# DESERILIZER.net
KiCad netlist of a schematic drawn in Altium Designer
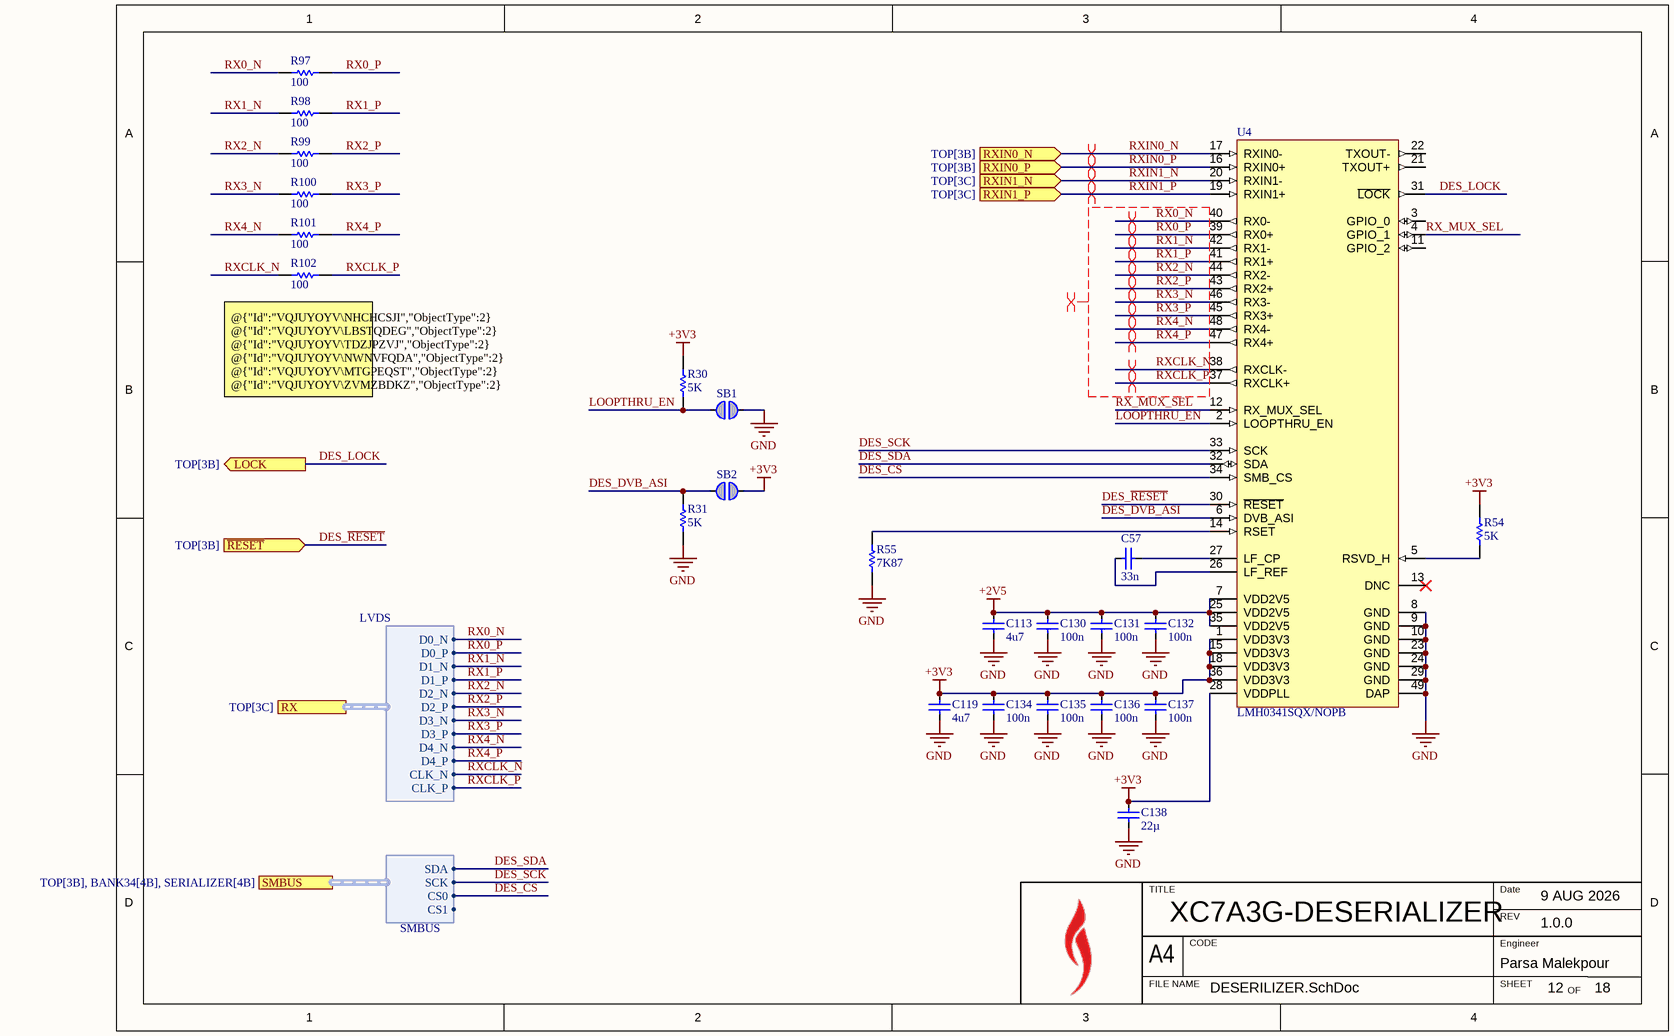
[diagram p0: DESERILIZER.SchDoc]

(export (version "E")
  (design (tool "Eeschema 10.0.6"))
  (components
    (comp (ref "C57")
      (value "33n")
      (footprint "pcblib1:FP-GCM155-0_05-MFG")
      (description "Ceramic Capacitor for Automotive 33nF ±10% 25VDC X7R 0402 Paper T/R")
      (fields (field (name "TOLERANCE") "10%") (field (name "Comment") "GCM155R71E333KA55D"))
      (libsource (lib "Schlib1") (part "GCM155R71E333KA55D"))
    )
    (comp (ref "C113")
      (value "4u7")
      (footprint "FP-C1005-050-0_20-0_10-IPC_C")
      (description "MLCC  4.7UF ±20 10V X5R 0402")
      (fields (field (name "TOLERANCE") "10%") (field (name "PART NUMBER") "C1005X5R1A475K050BE"))
      (libsource (lib "Schlib1") (part "C1005X5R1A475K050BE"))
    )
    (comp (ref "C119")
      (value "4u7")
      (footprint "FP-C1005-050-0_20-0_10-IPC_C")
      (description "MLCC  4.7UF ±20 10V X5R 0402")
      (fields (field (name "TOLERANCE") "10%") (field (name "PART NUMBER") "C1005X5R1A475K050BE"))
      (libsource (lib "Schlib1") (part "C1005X5R1A475K050BE"))
    )
    (comp (ref "C130")
      (value "100n")
      (footprint "FP-C1005-050-0_05-IPC_C")
      (description "MLCC 100nF ±10% 50V X7R SMD 0402")
      (fields (field (name "VOLTAGE") "50V") (field (name "TOLERANCE") "10%"))
      (libsource (lib "Schlib1") (part "C1005X7R1H104K050BB"))
    )
    (comp (ref "C131")
      (value "100n")
      (footprint "FP-C1005-050-0_05-IPC_C")
      (description "MLCC 100nF ±10% 50V X7R SMD 0402")
      (fields (field (name "VOLTAGE") "50V") (field (name "TOLERANCE") "10%"))
      (libsource (lib "Schlib1") (part "C1005X7R1H104K050BB"))
    )
    (comp (ref "C132")
      (value "100n")
      (footprint "FP-C1005-050-0_05-IPC_C")
      (description "MLCC 100nF ±10% 50V X7R SMD 0402")
      (fields (field (name "VOLTAGE") "50V") (field (name "TOLERANCE") "10%"))
      (libsource (lib "Schlib1") (part "C1005X7R1H104K050BB"))
    )
    (comp (ref "C134")
      (value "100n")
      (footprint "FP-C1005-050-0_05-IPC_C")
      (description "MLCC 100nF ±10% 50V X7R SMD 0402")
      (fields (field (name "VOLTAGE") "50V") (field (name "TOLERANCE") "10%"))
      (libsource (lib "Schlib1") (part "C1005X7R1H104K050BB"))
    )
    (comp (ref "C135")
      (value "100n")
      (footprint "FP-C1005-050-0_05-IPC_C")
      (description "MLCC 100nF ±10% 50V X7R SMD 0402")
      (fields (field (name "VOLTAGE") "50V") (field (name "TOLERANCE") "10%"))
      (libsource (lib "Schlib1") (part "C1005X7R1H104K050BB"))
    )
    (comp (ref "C136")
      (value "100n")
      (footprint "FP-C1005-050-0_05-IPC_C")
      (description "MLCC 100nF ±10% 50V X7R SMD 0402")
      (fields (field (name "VOLTAGE") "50V") (field (name "TOLERANCE") "10%"))
      (libsource (lib "Schlib1") (part "C1005X7R1H104K050BB"))
    )
    (comp (ref "C137")
      (value "100n")
      (footprint "FP-C1005-050-0_05-IPC_C")
      (description "MLCC 100nF ±10% 50V X7R SMD 0402")
      (fields (field (name "VOLTAGE") "50V") (field (name "TOLERANCE") "10%"))
      (libsource (lib "Schlib1") (part "C1005X7R1H104K050BB"))
    )
    (comp (ref "C138")
      (value "22µ")
      (footprint "CAPC1608X100X20LL10")
      (description "MLCC 22 uF, ±20%, 6.3 V, -55 to 85 degC, 1608 (0603 Metric), RoHS, Tape and Reel")
      (fields
        (field (name "TOLERANCE") "±20%")
        (field (name "PCN PART NUMBER") "MLCCPartNumberChange30/Nov/2012")
      )
      (libsource (lib "Schlib1") (part "C1608X5R0J226M080AC"))
    )
    (comp (ref "R30")
      (value "5K")
      (footprint "RESC1005X40X25LL05T10")
      (description "62.5mW Thick Film Resistors 50V ±100ppm/℃ ±1% 5kΩ 0402 Chip Resistor - Surface Mount ROHS")
      (fields (field (name "MANUFACTURER") "Yageo / Phycomp") (field (name "PART NUMBER") "RC0402FR-075KL"))
      (libsource (lib "Schlib1") (part "RES"))
    )
    (comp (ref "R31")
      (value "5K")
      (footprint "RESC1005X40X25LL05T10")
      (description "62.5mW Thick Film Resistors 50V ±100ppm/℃ ±1% 5kΩ 0402 Chip Resistor - Surface Mount ROHS")
      (fields (field (name "MANUFACTURER") "Yageo / Phycomp") (field (name "PART NUMBER") "RC0402FR-075KL"))
      (libsource (lib "Schlib1") (part "RES"))
    )
    (comp (ref "R54")
      (value "5K")
      (footprint "RESC1005X40X25LL05T10")
      (description "62.5mW Thick Film Resistors 50V ±100ppm/℃ ±1% 5kΩ 0402 Chip Resistor - Surface Mount ROHS")
      (fields (field (name "MANUFACTURER") "Yageo / Phycomp") (field (name "PART NUMBER") "RC0402FR-075KL"))
      (libsource (lib "Schlib1") (part "RES"))
    )
    (comp (ref "R55")
      (value "7K87")
      (footprint "RESC1005X40X25LL05T10")
      (description "62.5mW Thick Film Resistors 50V ±100ppm/℃ ±1% 5kΩ 0402 Chip Resistor - Surface Mount ROHS")
      (fields (field (name "MANUFACTURER") "Yageo / Phycomp") (field (name "PART NUMBER") "RC0402FR-075KL"))
      (libsource (lib "Schlib1") (part "RES"))
    )
    (comp (ref "R97")
      (value "100")
      (footprint "pcblib1:RESC1005X40X25LL05T10")
      (fields (field (name "PART NUMBER") "RC0402FR-07100RL") (field (name "MANUFACTURER") "Yageo / Phycomp"))
      (libsource (lib "Schlib1") (part "RC0402FR-07100RL"))
    )
    (comp (ref "R98")
      (value "100")
      (footprint "pcblib1:RESC1005X40X25LL05T10")
      (fields (field (name "PART NUMBER") "RC0402FR-07100RL") (field (name "MANUFACTURER") "Yageo / Phycomp"))
      (libsource (lib "Schlib1") (part "RC0402FR-07100RL"))
    )
    (comp (ref "R99")
      (value "100")
      (footprint "pcblib1:RESC1005X40X25LL05T10")
      (fields (field (name "PART NUMBER") "RC0402FR-07100RL") (field (name "MANUFACTURER") "Yageo / Phycomp"))
      (libsource (lib "Schlib1") (part "RC0402FR-07100RL"))
    )
    (comp (ref "R100")
      (value "100")
      (footprint "pcblib1:RESC1005X40X25LL05T10")
      (fields (field (name "PART NUMBER") "RC0402FR-07100RL") (field (name "MANUFACTURER") "Yageo / Phycomp"))
      (libsource (lib "Schlib1") (part "RC0402FR-07100RL"))
    )
    (comp (ref "R101")
      (value "100")
      (footprint "pcblib1:RESC1005X40X25LL05T10")
      (fields (field (name "PART NUMBER") "RC0402FR-07100RL") (field (name "MANUFACTURER") "Yageo / Phycomp"))
      (libsource (lib "Schlib1") (part "RC0402FR-07100RL"))
    )
    (comp (ref "R102")
      (value "100")
      (footprint "pcblib1:RESC1005X40X25LL05T10")
      (fields (field (name "PART NUMBER") "RC0402FR-07100RL") (field (name "MANUFACTURER") "Yageo / Phycomp"))
      (libsource (lib "Schlib1") (part "RC0402FR-07100RL"))
    )
    (comp (ref "SB1")
      (value "Solderbridge")
      (footprint "Solderbridge")
      (fields (field (name "MANUFACTURER") "N.A."))
      (libsource (lib "ParsaLibrary") (part "Solderbridge_1"))
    )
    (comp (ref "SB2")
      (value "Solderbridge")
      (footprint "Solderbridge")
      (fields (field (name "MANUFACTURER") "N.A."))
      (libsource (lib "ParsaLibrary") (part "Solderbridge_1"))
    )
    (comp (ref "U4")
      (value "LMH0341SQX/NOPB")
      (footprint "RHS0048A_V")
      (description "3 Gbps, HD, SD, DVB-ASI SDI Deserializer with Loopthrough and LVDS Interface, 48-pin LLP, Pb-Free")
      (fields
        (field (name "MANUFACTURER") "Texas Instruments")
        (field (name "MANUFACTURER PART NUMBER") "RC0402FR-075KL")
      )
      (libsource (lib "Schlib1") (part "LMH0341SQX/NOPB"))
    )
  )
  (nets
    (net (code "3") (name "+2V5") (class "Default")
      (node (ref "C113") (pin "1") (pinfunction "1_1") (pintype "passive"))
      (node (ref "C130") (pin "1") (pinfunction "1_1") (pintype "passive"))
      (node (ref "C131") (pin "1") (pinfunction "1_1") (pintype "passive"))
      (node (ref "C132") (pin "1") (pinfunction "1_1") (pintype "passive"))
      (node (ref "U4") (pin "25") (pinfunction "VDD2V5_25") (pintype "power_in"))
      (node (ref "U4") (pin "35") (pinfunction "VDD2V5_35") (pintype "power_in"))
      (node (ref "U4") (pin "7") (pinfunction "VDD2V5_7") (pintype "power_in"))
    )
    (net (code "4") (name "+3V3") (class "Default")
      (node (ref "C119") (pin "1") (pinfunction "1_1") (pintype "passive"))
      (node (ref "C134") (pin "1") (pinfunction "1_1") (pintype "passive"))
      (node (ref "C135") (pin "1") (pinfunction "1_1") (pintype "passive"))
      (node (ref "C136") (pin "1") (pinfunction "1_1") (pintype "passive"))
      (node (ref "C137") (pin "1") (pinfunction "1_1") (pintype "passive"))
      (node (ref "C138") (pin "2") (pinfunction "2_2") (pintype "passive"))
      (node (ref "R30") (pin "1") (pinfunction "1_1") (pintype "passive"))
      (node (ref "R54") (pin "1") (pinfunction "1_1") (pintype "passive"))
      (node (ref "SB2") (pin "1") (pinfunction "0_1") (pintype "passive"))
      (node (ref "U4") (pin "1") (pinfunction "VDD3V3_1") (pintype "power_in"))
      (node (ref "U4") (pin "15") (pinfunction "VDD3V3_15") (pintype "power_in"))
      (node (ref "U4") (pin "18") (pinfunction "VDD3V3_18") (pintype "power_in"))
      (node (ref "U4") (pin "28") (pinfunction "VDDPLL_28") (pintype "power_in"))
      (node (ref "U4") (pin "36") (pinfunction "VDD3V3_36") (pintype "power_in"))
    )
    (net (code "5") (name "/DES_CS") (class "Default")
      (node (ref "U4") (pin "34") (pinfunction "SMB_CS_34") (pintype "input"))
    )
    (net (code "6") (name "/DES_DVB_ASI") (class "Default")
      (node (ref "R31") (pin "1") (pinfunction "1_1") (pintype "passive"))
      (node (ref "SB2") (pin "2") (pinfunction "1_2") (pintype "passive"))
      (node (ref "U4") (pin "6") (pinfunction "DVB_ASI_6") (pintype "input"))
    )
    (net (code "7") (name "/DES_LOCK") (class "Default")
      (node (ref "U4") (pin "31") (pinfunction "~{LOCK}_31") (pintype "output"))
    )
    (net (code "8") (name "/DES_SCK") (class "Default")
      (node (ref "U4") (pin "33") (pinfunction "SCK_33") (pintype "input"))
    )
    (net (code "9") (name "/DES_SDA") (class "Default")
      (node (ref "U4") (pin "32") (pinfunction "SDA_32") (pintype "bidirectional"))
    )
    (net (code "10") (name "/DES_~{RESET}") (class "Default")
      (node (ref "U4") (pin "30") (pinfunction "~{RESET}_30") (pintype "input"))
    )
    (net (code "11") (name "/LOOPTHRU_EN") (class "Default")
      (node (ref "R30") (pin "2") (pinfunction "2_2") (pintype "passive"))
      (node (ref "SB1") (pin "2") (pinfunction "1_2") (pintype "passive"))
      (node (ref "U4") (pin "2") (pinfunction "LOOPTHRU_EN_2") (pintype "input"))
    )
    (net (code "12") (name "/RX0_N") (class "Default")
      (node (ref "R97") (pin "1") (pinfunction "1_1") (pintype "passive"))
      (node (ref "U4") (pin "40") (pinfunction "RX0-_40") (pintype "output"))
    )
    (net (code "13") (name "/RX0_P") (class "Default")
      (node (ref "R97") (pin "2") (pinfunction "2_2") (pintype "passive"))
      (node (ref "U4") (pin "39") (pinfunction "RX0+_39") (pintype "output"))
    )
    (net (code "14") (name "/RX1_N") (class "Default")
      (node (ref "R98") (pin "1") (pinfunction "1_1") (pintype "passive"))
      (node (ref "U4") (pin "42") (pinfunction "RX1-_42") (pintype "output"))
    )
    (net (code "15") (name "/RX1_P") (class "Default")
      (node (ref "R98") (pin "2") (pinfunction "2_2") (pintype "passive"))
      (node (ref "U4") (pin "41") (pinfunction "RX1+_41") (pintype "output"))
    )
    (net (code "16") (name "/RX2_N") (class "Default")
      (node (ref "R99") (pin "1") (pinfunction "1_1") (pintype "passive"))
      (node (ref "U4") (pin "44") (pinfunction "RX2-_44") (pintype "output"))
    )
    (net (code "17") (name "/RX2_P") (class "Default")
      (node (ref "R99") (pin "2") (pinfunction "2_2") (pintype "passive"))
      (node (ref "U4") (pin "43") (pinfunction "RX2+_43") (pintype "output"))
    )
    (net (code "18") (name "/RX3_N") (class "Default")
      (node (ref "R100") (pin "2") (pinfunction "2_2") (pintype "passive"))
      (node (ref "U4") (pin "46") (pinfunction "RX3-_46") (pintype "output"))
    )
    (net (code "19") (name "/RX3_P") (class "Default")
      (node (ref "R100") (pin "1") (pinfunction "1_1") (pintype "passive"))
      (node (ref "U4") (pin "45") (pinfunction "RX3+_45") (pintype "output"))
    )
    (net (code "20") (name "/RX4_N") (class "Default")
      (node (ref "R101") (pin "2") (pinfunction "2_2") (pintype "passive"))
      (node (ref "U4") (pin "48") (pinfunction "RX4-_48") (pintype "output"))
    )
    (net (code "21") (name "/RX4_P") (class "Default")
      (node (ref "R101") (pin "1") (pinfunction "1_1") (pintype "passive"))
      (node (ref "U4") (pin "47") (pinfunction "RX4+_47") (pintype "output"))
    )
    (net (code "22") (name "/RXCLK_N") (class "Default")
      (node (ref "R102") (pin "1") (pinfunction "1_1") (pintype "passive"))
      (node (ref "U4") (pin "38") (pinfunction "RXCLK-_38") (pintype "output"))
    )
    (net (code "23") (name "/RXCLK_P") (class "Default")
      (node (ref "R102") (pin "2") (pinfunction "2_2") (pintype "passive"))
      (node (ref "U4") (pin "37") (pinfunction "RXCLK+_37") (pintype "output"))
    )
    (net (code "24") (name "/RXIN0_N") (class "Default")
      (node (ref "U4") (pin "17") (pinfunction "RXIN0-_17") (pintype "input"))
    )
    (net (code "25") (name "/RXIN0_P") (class "Default")
      (node (ref "U4") (pin "16") (pinfunction "RXIN0+_16") (pintype "input"))
    )
    (net (code "26") (name "/RXIN1_N") (class "Default")
      (node (ref "U4") (pin "20") (pinfunction "RXIN1-_20") (pintype "input"))
    )
    (net (code "27") (name "/RXIN1_P") (class "Default")
      (node (ref "U4") (pin "19") (pinfunction "RXIN1+_19") (pintype "input"))
    )
    (net (code "28") (name "/RX_MUX_SEL") (class "Default")
      (node (ref "U4") (pin "12") (pinfunction "RX_MUX_SEL_12") (pintype "input"))
      (node (ref "U4") (pin "4") (pinfunction "GPIO_1_4") (pintype "bidirectional"))
    )
    (net (code "31") (name "GND") (class "Default")
      (node (ref "C113") (pin "2") (pinfunction "2_2") (pintype "passive"))
      (node (ref "C119") (pin "2") (pinfunction "2_2") (pintype "passive"))
      (node (ref "C130") (pin "2") (pinfunction "2_2") (pintype "passive"))
      (node (ref "C131") (pin "2") (pinfunction "2_2") (pintype "passive"))
      (node (ref "C132") (pin "2") (pinfunction "2_2") (pintype "passive"))
      (node (ref "C134") (pin "2") (pinfunction "2_2") (pintype "passive"))
      (node (ref "C135") (pin "2") (pinfunction "2_2") (pintype "passive"))
      (node (ref "C136") (pin "2") (pinfunction "2_2") (pintype "passive"))
      (node (ref "C137") (pin "2") (pinfunction "2_2") (pintype "passive"))
      (node (ref "C138") (pin "1") (pinfunction "1_1") (pintype "passive"))
      (node (ref "R31") (pin "2") (pinfunction "2_2") (pintype "passive"))
      (node (ref "R55") (pin "2") (pinfunction "2_2") (pintype "passive"))
      (node (ref "SB1") (pin "1") (pinfunction "0_1") (pintype "passive"))
      (node (ref "U4") (pin "10") (pinfunction "GND_10") (pintype "power_in"))
      (node (ref "U4") (pin "23") (pinfunction "GND_23") (pintype "power_in"))
      (node (ref "U4") (pin "24") (pinfunction "GND_24") (pintype "power_in"))
      (node (ref "U4") (pin "29") (pinfunction "GND_29") (pintype "power_in"))
      (node (ref "U4") (pin "49") (pinfunction "DAP_49") (pintype "power_in"))
      (node (ref "U4") (pin "8") (pinfunction "GND_8") (pintype "power_in"))
      (node (ref "U4") (pin "9") (pinfunction "GND_9") (pintype "power_in"))
    )
    (net (code "32") (name "Net-(U4-LF_CP)") (class "Default")
      (node (ref "C57") (pin "1") (pinfunction "1_1") (pintype "passive"))
      (node (ref "U4") (pin "27") (pinfunction "LF_CP_27") (pintype "passive"))
    )
    (net (code "33") (name "Net-(U4-LF_REF)") (class "Default")
      (node (ref "C57") (pin "2") (pinfunction "2_2") (pintype "passive"))
      (node (ref "U4") (pin "26") (pinfunction "LF_REF_26") (pintype "passive"))
    )
    (net (code "34") (name "Net-(U4-RSET)") (class "Default")
      (node (ref "R55") (pin "1") (pinfunction "1_1") (pintype "passive"))
      (node (ref "U4") (pin "14") (pinfunction "RSET_14") (pintype "input"))
    )
    (net (code "35") (name "Net-(U4-RSVD_H)") (class "Default")
      (node (ref "R54") (pin "2") (pinfunction "2_2") (pintype "passive"))
      (node (ref "U4") (pin "5") (pinfunction "RSVD_H_5") (pintype "input"))
    )
    (net (code "36") (name "unconnected-(U4-DNC-Pad13)") (class "Default")
      (node (ref "U4") (pin "13") (pinfunction "DNC_13") (pintype "passive+no_connect"))
    )
    (net (code "37") (name "unconnected-(U4-GPIO_0-Pad3)") (class "Default")
      (node (ref "U4") (pin "3") (pinfunction "GPIO_0_3") (pintype "bidirectional"))
    )
    (net (code "38") (name "unconnected-(U4-GPIO_2-Pad11)") (class "Default")
      (node (ref "U4") (pin "11") (pinfunction "GPIO_2_11") (pintype "bidirectional"))
    )
    (net (code "39") (name "unconnected-(U4-TXOUT+-Pad21)") (class "Default")
      (node (ref "U4") (pin "21") (pinfunction "TXOUT+_21") (pintype "output"))
    )
    (net (code "40") (name "unconnected-(U4-TXOUT--Pad22)") (class "Default")
      (node (ref "U4") (pin "22") (pinfunction "TXOUT-_22") (pintype "output"))
    )
  )
)
